# ProgramMemory.net
KiCad netlist of a schematic drawn in EAGLE
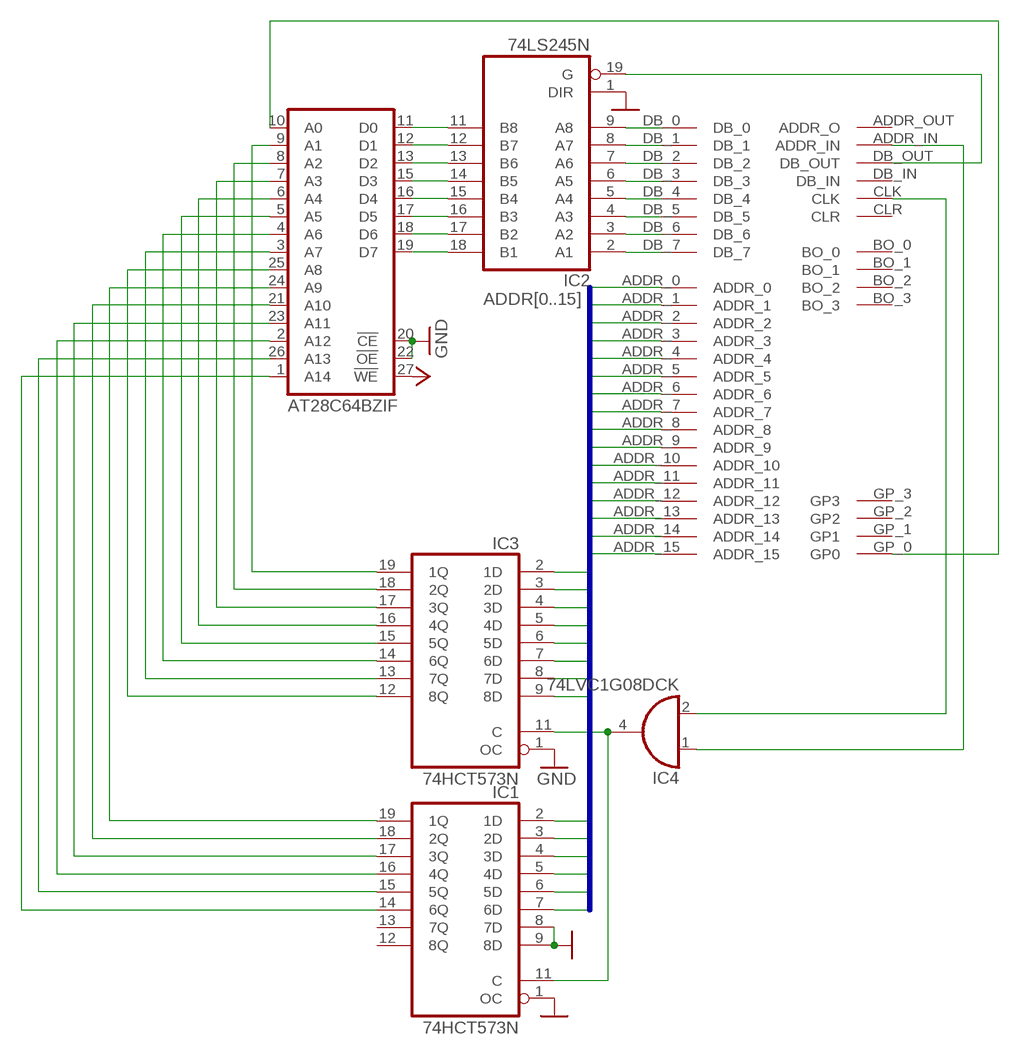
[diagram p0: schematic, sheet 1]

(export (version "E")
  (design (tool "Eeschema 10.0.6"))
  (components
    (comp (ref "IC1")
      (value "74HCT573N")
      (footprint "eagle-import:DIL20")
      (libsource (lib "eagle-import") (part "74573NHCT"))
    )
    (comp (ref "IC2")
      (value "74LS245N")
      (footprint "eagle-import:DIL20")
      (libsource (lib "eagle-import") (part "74245NLS"))
    )
    (comp (ref "IC3")
      (value "74HCT573N")
      (footprint "eagle-import:DIL20")
      (libsource (lib "eagle-import") (part "74573NHCT"))
    )
    (comp (ref "IC4")
      (value "74LVC1G08DCK")
      (footprint "eagle-import:SC70-5")
      (libsource (lib "eagle-import") (part "741G08DCKLVC"))
    )
    (comp (ref "U$1")
      (value "BACKPLATE_INTERFACEEDGE_FINGER")
      (footprint "eagle-import:BACK_INTERFACE-FOOT")
      (libsource (lib "eagle-import") (part "BACKPLATE_INTERFACEEDGE_FINGER"))
    )
    (comp (ref "U$2")
      (value "AT28C64BZIF")
      (footprint "eagle-import:28-WIDE_ZIF-FOOT")
      (libsource (lib "eagle-import") (part "AT28C64BZIF"))
    )
  )
  (nets
    (net (code "3") (name "/ADDR0") (class "Default")
      (node (ref "IC3") (pin "2") (pinfunction "1D_2") (pintype "input"))
      (node (ref "U$1") (pin "ADDR_0") (pinfunction "ADDR_0_ADDR_0") (pintype "bidirectional"))
    )
    (net (code "4") (name "/ADDR1") (class "Default")
      (node (ref "IC3") (pin "3") (pinfunction "2D_3") (pintype "input"))
      (node (ref "U$1") (pin "ADDR_1") (pinfunction "ADDR_1_ADDR_1") (pintype "bidirectional"))
    )
    (net (code "5") (name "/ADDR2") (class "Default")
      (node (ref "IC3") (pin "4") (pinfunction "3D_4") (pintype "input"))
      (node (ref "U$1") (pin "ADDR_2") (pinfunction "ADDR_2_ADDR_2") (pintype "bidirectional"))
    )
    (net (code "6") (name "/ADDR3") (class "Default")
      (node (ref "IC3") (pin "5") (pinfunction "4D_5") (pintype "input"))
      (node (ref "U$1") (pin "ADDR_3") (pinfunction "ADDR_3_ADDR_3") (pintype "bidirectional"))
    )
    (net (code "7") (name "/ADDR4") (class "Default")
      (node (ref "IC3") (pin "6") (pinfunction "5D_6") (pintype "input"))
      (node (ref "U$1") (pin "ADDR_4") (pinfunction "ADDR_4_ADDR_4") (pintype "bidirectional"))
    )
    (net (code "8") (name "/ADDR5") (class "Default")
      (node (ref "IC3") (pin "7") (pinfunction "6D_7") (pintype "input"))
      (node (ref "U$1") (pin "ADDR_5") (pinfunction "ADDR_5_ADDR_5") (pintype "bidirectional"))
    )
    (net (code "9") (name "/ADDR6") (class "Default")
      (node (ref "IC3") (pin "8") (pinfunction "7D_8") (pintype "input"))
      (node (ref "U$1") (pin "ADDR_6") (pinfunction "ADDR_6_ADDR_6") (pintype "bidirectional"))
    )
    (net (code "10") (name "/ADDR7") (class "Default")
      (node (ref "IC3") (pin "9") (pinfunction "8D_9") (pintype "input"))
      (node (ref "U$1") (pin "ADDR_7") (pinfunction "ADDR_7_ADDR_7") (pintype "bidirectional"))
    )
    (net (code "11") (name "/ADDR8") (class "Default")
      (node (ref "IC1") (pin "2") (pinfunction "1D_2") (pintype "input"))
      (node (ref "U$1") (pin "ADDR_8") (pinfunction "ADDR_8_ADDR_8") (pintype "bidirectional"))
    )
    (net (code "12") (name "/ADDR9") (class "Default")
      (node (ref "IC1") (pin "3") (pinfunction "2D_3") (pintype "input"))
      (node (ref "U$1") (pin "ADDR_9") (pinfunction "ADDR_9_ADDR_9") (pintype "bidirectional"))
    )
    (net (code "13") (name "/ADDR10") (class "Default")
      (node (ref "IC1") (pin "4") (pinfunction "3D_4") (pintype "input"))
      (node (ref "U$1") (pin "ADDR_10") (pinfunction "ADDR_10_ADDR_10") (pintype "bidirectional"))
    )
    (net (code "14") (name "/ADDR11") (class "Default")
      (node (ref "IC1") (pin "5") (pinfunction "4D_5") (pintype "input"))
      (node (ref "U$1") (pin "ADDR_11") (pinfunction "ADDR_11_ADDR_11") (pintype "bidirectional"))
    )
    (net (code "15") (name "/ADDR12") (class "Default")
      (node (ref "IC1") (pin "6") (pinfunction "5D_6") (pintype "input"))
      (node (ref "U$1") (pin "ADDR_12") (pinfunction "ADDR_12_ADDR_12") (pintype "bidirectional"))
    )
    (net (code "16") (name "/ADDR13") (class "Default")
      (node (ref "IC1") (pin "7") (pinfunction "6D_7") (pintype "input"))
      (node (ref "U$1") (pin "ADDR_13") (pinfunction "ADDR_13_ADDR_13") (pintype "bidirectional"))
    )
    (net (code "18") (name "GND") (class "Default")
      (node (ref "IC1") (pin "1") (pinfunction "OC_1") (pintype "input"))
      (node (ref "IC1") (pin "8") (pinfunction "7D_8") (pintype "input"))
      (node (ref "IC1") (pin "9") (pinfunction "8D_9") (pintype "input"))
      (node (ref "IC2") (pin "1") (pinfunction "DIR_1") (pintype "input"))
      (node (ref "IC3") (pin "1") (pinfunction "OC_1") (pintype "input"))
      (node (ref "U$2") (pin "20") (pinfunction "~{CE}_20") (pintype "input"))
      (node (ref "U$2") (pin "22") (pinfunction "~{OE}_22") (pintype "input"))
    )
    (net (code "19") (name "Net-(IC1A-1Q)") (class "Default")
      (node (ref "IC1") (pin "19") (pinfunction "1Q_19") (pintype "tri_state"))
      (node (ref "U$2") (pin "24") (pinfunction "A9_24") (pintype "input"))
    )
    (net (code "20") (name "Net-(IC1A-2Q)") (class "Default")
      (node (ref "IC1") (pin "18") (pinfunction "2Q_18") (pintype "tri_state"))
      (node (ref "U$2") (pin "21") (pinfunction "A10_21") (pintype "input"))
    )
    (net (code "21") (name "Net-(IC1A-3Q)") (class "Default")
      (node (ref "IC1") (pin "17") (pinfunction "3Q_17") (pintype "tri_state"))
      (node (ref "U$2") (pin "23") (pinfunction "A11_23") (pintype "input"))
    )
    (net (code "22") (name "Net-(IC1A-4Q)") (class "Default")
      (node (ref "IC1") (pin "16") (pinfunction "4Q_16") (pintype "tri_state"))
      (node (ref "U$2") (pin "2") (pinfunction "A12_2") (pintype "input"))
    )
    (net (code "23") (name "Net-(IC1A-5Q)") (class "Default")
      (node (ref "IC1") (pin "15") (pinfunction "5Q_15") (pintype "tri_state"))
      (node (ref "U$2") (pin "26") (pinfunction "A13_26") (pintype "input"))
    )
    (net (code "24") (name "Net-(IC1A-6Q)") (class "Default")
      (node (ref "IC1") (pin "14") (pinfunction "6Q_14") (pintype "tri_state"))
      (node (ref "U$2") (pin "1") (pinfunction "A14_1") (pintype "input"))
    )
    (net (code "25") (name "Net-(IC1A-C)") (class "Default")
      (node (ref "IC1") (pin "11") (pinfunction "C_11") (pintype "input"))
      (node (ref "IC3") (pin "11") (pinfunction "C_11") (pintype "input"))
      (node (ref "IC4") (pin "4") (pinfunction "O_4") (pintype "output"))
    )
    (net (code "26") (name "Net-(IC2A-A1)") (class "Default")
      (node (ref "IC2") (pin "2") (pinfunction "A1_2") (pintype "bidirectional"))
      (node (ref "U$1") (pin "DB_7") (pinfunction "DB_7_DB_7") (pintype "bidirectional"))
    )
    (net (code "27") (name "Net-(IC2A-A2)") (class "Default")
      (node (ref "IC2") (pin "3") (pinfunction "A2_3") (pintype "bidirectional"))
      (node (ref "U$1") (pin "DB_6") (pinfunction "DB_6_DB_6") (pintype "bidirectional"))
    )
    (net (code "28") (name "Net-(IC2A-A3)") (class "Default")
      (node (ref "IC2") (pin "4") (pinfunction "A3_4") (pintype "bidirectional"))
      (node (ref "U$1") (pin "DB_5") (pinfunction "DB_5_DB_5") (pintype "bidirectional"))
    )
    (net (code "29") (name "Net-(IC2A-A4)") (class "Default")
      (node (ref "IC2") (pin "5") (pinfunction "A4_5") (pintype "bidirectional"))
      (node (ref "U$1") (pin "DB_4") (pinfunction "DB_4_DB_4") (pintype "bidirectional"))
    )
    (net (code "30") (name "Net-(IC2A-A5)") (class "Default")
      (node (ref "IC2") (pin "6") (pinfunction "A5_6") (pintype "bidirectional"))
      (node (ref "U$1") (pin "DB_3") (pinfunction "DB_3_DB_3") (pintype "bidirectional"))
    )
    (net (code "31") (name "Net-(IC2A-A6)") (class "Default")
      (node (ref "IC2") (pin "7") (pinfunction "A6_7") (pintype "bidirectional"))
      (node (ref "U$1") (pin "DB_2") (pinfunction "DB_2_DB_2") (pintype "bidirectional"))
    )
    (net (code "32") (name "Net-(IC2A-A7)") (class "Default")
      (node (ref "IC2") (pin "8") (pinfunction "A7_8") (pintype "bidirectional"))
      (node (ref "U$1") (pin "DB_1") (pinfunction "DB_1_DB_1") (pintype "bidirectional"))
    )
    (net (code "33") (name "Net-(IC2A-A8)") (class "Default")
      (node (ref "IC2") (pin "9") (pinfunction "A8_9") (pintype "bidirectional"))
      (node (ref "U$1") (pin "DB_0") (pinfunction "DB_0_DB_0") (pintype "bidirectional"))
    )
    (net (code "34") (name "Net-(IC2A-B1)") (class "Default")
      (node (ref "IC2") (pin "18") (pinfunction "B1_18") (pintype "bidirectional"))
      (node (ref "U$2") (pin "19") (pinfunction "D7_19") (pintype "bidirectional"))
    )
    (net (code "35") (name "Net-(IC2A-B2)") (class "Default")
      (node (ref "IC2") (pin "17") (pinfunction "B2_17") (pintype "bidirectional"))
      (node (ref "U$2") (pin "18") (pinfunction "D6_18") (pintype "bidirectional"))
    )
    (net (code "36") (name "Net-(IC2A-B3)") (class "Default")
      (node (ref "IC2") (pin "16") (pinfunction "B3_16") (pintype "bidirectional"))
      (node (ref "U$2") (pin "17") (pinfunction "D5_17") (pintype "bidirectional"))
    )
    (net (code "37") (name "Net-(IC2A-B4)") (class "Default")
      (node (ref "IC2") (pin "15") (pinfunction "B4_15") (pintype "bidirectional"))
      (node (ref "U$2") (pin "16") (pinfunction "D4_16") (pintype "bidirectional"))
    )
    (net (code "38") (name "Net-(IC2A-B5)") (class "Default")
      (node (ref "IC2") (pin "14") (pinfunction "B5_14") (pintype "bidirectional"))
      (node (ref "U$2") (pin "15") (pinfunction "D3_15") (pintype "bidirectional"))
    )
    (net (code "39") (name "Net-(IC2A-B6)") (class "Default")
      (node (ref "IC2") (pin "13") (pinfunction "B6_13") (pintype "bidirectional"))
      (node (ref "U$2") (pin "13") (pinfunction "D2_13") (pintype "bidirectional"))
    )
    (net (code "40") (name "Net-(IC2A-B7)") (class "Default")
      (node (ref "IC2") (pin "12") (pinfunction "B7_12") (pintype "bidirectional"))
      (node (ref "U$2") (pin "12") (pinfunction "D1_12") (pintype "bidirectional"))
    )
    (net (code "41") (name "Net-(IC2A-B8)") (class "Default")
      (node (ref "IC2") (pin "11") (pinfunction "B8_11") (pintype "bidirectional"))
      (node (ref "U$2") (pin "11") (pinfunction "D0_11") (pintype "bidirectional"))
    )
    (net (code "42") (name "Net-(IC2A-G)") (class "Default")
      (node (ref "IC2") (pin "19") (pinfunction "G_19") (pintype "input"))
      (node (ref "U$1") (pin "DB_OUT") (pinfunction "DB_OUT_DB_OUT") (pintype "bidirectional"))
    )
    (net (code "43") (name "Net-(IC3A-1Q)") (class "Default")
      (node (ref "IC3") (pin "19") (pinfunction "1Q_19") (pintype "tri_state"))
      (node (ref "U$2") (pin "9") (pinfunction "A1_9") (pintype "input"))
    )
    (net (code "44") (name "Net-(IC3A-2Q)") (class "Default")
      (node (ref "IC3") (pin "18") (pinfunction "2Q_18") (pintype "tri_state"))
      (node (ref "U$2") (pin "8") (pinfunction "A2_8") (pintype "input"))
    )
    (net (code "45") (name "Net-(IC3A-3Q)") (class "Default")
      (node (ref "IC3") (pin "17") (pinfunction "3Q_17") (pintype "tri_state"))
      (node (ref "U$2") (pin "7") (pinfunction "A3_7") (pintype "input"))
    )
    (net (code "46") (name "Net-(IC3A-4Q)") (class "Default")
      (node (ref "IC3") (pin "16") (pinfunction "4Q_16") (pintype "tri_state"))
      (node (ref "U$2") (pin "6") (pinfunction "A4_6") (pintype "input"))
    )
    (net (code "47") (name "Net-(IC3A-5Q)") (class "Default")
      (node (ref "IC3") (pin "15") (pinfunction "5Q_15") (pintype "tri_state"))
      (node (ref "U$2") (pin "5") (pinfunction "A5_5") (pintype "input"))
    )
    (net (code "48") (name "Net-(IC3A-6Q)") (class "Default")
      (node (ref "IC3") (pin "14") (pinfunction "6Q_14") (pintype "tri_state"))
      (node (ref "U$2") (pin "4") (pinfunction "A6_4") (pintype "input"))
    )
    (net (code "49") (name "Net-(IC3A-7Q)") (class "Default")
      (node (ref "IC3") (pin "13") (pinfunction "7Q_13") (pintype "tri_state"))
      (node (ref "U$2") (pin "3") (pinfunction "A7_3") (pintype "input"))
    )
    (net (code "50") (name "Net-(IC3A-8Q)") (class "Default")
      (node (ref "IC3") (pin "12") (pinfunction "8Q_12") (pintype "tri_state"))
      (node (ref "U$2") (pin "25") (pinfunction "A8_25") (pintype "input"))
    )
    (net (code "51") (name "Net-(IC4A-I0)") (class "Default")
      (node (ref "IC4") (pin "1") (pinfunction "I0_1") (pintype "input"))
      (node (ref "U$1") (pin "ADDR_IN") (pinfunction "ADDR_IN_ADDR_IN") (pintype "bidirectional"))
    )
    (net (code "52") (name "Net-(IC4A-I1)") (class "Default")
      (node (ref "IC4") (pin "2") (pinfunction "I1_2") (pintype "input"))
      (node (ref "U$1") (pin "CLK") (pinfunction "CLK_CLK") (pintype "bidirectional"))
    )
    (net (code "53") (name "Net-(U$1A-GP0)") (class "Default")
      (node (ref "U$1") (pin "GP_0") (pinfunction "GP0_GP_0") (pintype "bidirectional"))
      (node (ref "U$2") (pin "10") (pinfunction "A0_10") (pintype "input"))
    )
    (net (code "54") (name "VCC") (class "Default")
      (node (ref "U$2") (pin "27") (pinfunction "~{WE}_27") (pintype "input"))
    )
    (net (code "55") (name "unconnected-(IC1A-7Q-Pad13)") (class "Default")
      (node (ref "IC1") (pin "13") (pinfunction "7Q_13") (pintype "tri_state"))
    )
    (net (code "56") (name "unconnected-(IC1A-8Q-Pad12)") (class "Default")
      (node (ref "IC1") (pin "12") (pinfunction "8Q_12") (pintype "tri_state"))
    )
    (net (code "57") (name "unconnected-(U$1-PadADDR_14)") (class "Default")
      (node (ref "U$1") (pin "ADDR_14") (pinfunction "ADDR_14_ADDR_14") (pintype "bidirectional"))
    )
    (net (code "58") (name "unconnected-(U$1-PadADDR_15)") (class "Default")
      (node (ref "U$1") (pin "ADDR_15") (pinfunction "ADDR_15_ADDR_15") (pintype "bidirectional"))
    )
    (net (code "59") (name "unconnected-(U$1-PadBO_0)") (class "Default")
      (node (ref "U$1") (pin "BO_0") (pinfunction "BO_0_BO_0") (pintype "bidirectional"))
    )
    (net (code "60") (name "unconnected-(U$1-PadBO_1)") (class "Default")
      (node (ref "U$1") (pin "BO_1") (pinfunction "BO_1_BO_1") (pintype "bidirectional"))
    )
    (net (code "61") (name "unconnected-(U$1-PadBO_2)") (class "Default")
      (node (ref "U$1") (pin "BO_2") (pinfunction "BO_2_BO_2") (pintype "bidirectional"))
    )
    (net (code "62") (name "unconnected-(U$1-PadBO_3)") (class "Default")
      (node (ref "U$1") (pin "BO_3") (pinfunction "BO_3_BO_3") (pintype "bidirectional"))
    )
    (net (code "63") (name "unconnected-(U$1-PadCLR)") (class "Default")
      (node (ref "U$1") (pin "CLR") (pinfunction "CLR_CLR") (pintype "bidirectional"))
    )
    (net (code "64") (name "unconnected-(U$1-PadDB_IN)") (class "Default")
      (node (ref "U$1") (pin "DB_IN") (pinfunction "DB_IN_DB_IN") (pintype "bidirectional"))
    )
    (net (code "65") (name "unconnected-(U$1A-ADDR_O-PadADDR_OUT)") (class "Default")
      (node (ref "U$1") (pin "ADDR_OUT") (pinfunction "ADDR_O_ADDR_OUT") (pintype "bidirectional"))
    )
    (net (code "66") (name "unconnected-(U$1A-GP1-PadGP_1)") (class "Default")
      (node (ref "U$1") (pin "GP_1") (pinfunction "GP1_GP_1") (pintype "bidirectional"))
    )
    (net (code "67") (name "unconnected-(U$1A-GP2-PadGP_2)") (class "Default")
      (node (ref "U$1") (pin "GP_2") (pinfunction "GP2_GP_2") (pintype "bidirectional"))
    )
    (net (code "68") (name "unconnected-(U$1A-GP3-PadGP_3)") (class "Default")
      (node (ref "U$1") (pin "GP_3") (pinfunction "GP3_GP_3") (pintype "bidirectional"))
    )
  )
)
